# Top_Level.net
KiCad netlist of a schematic drawn in Altium Designer
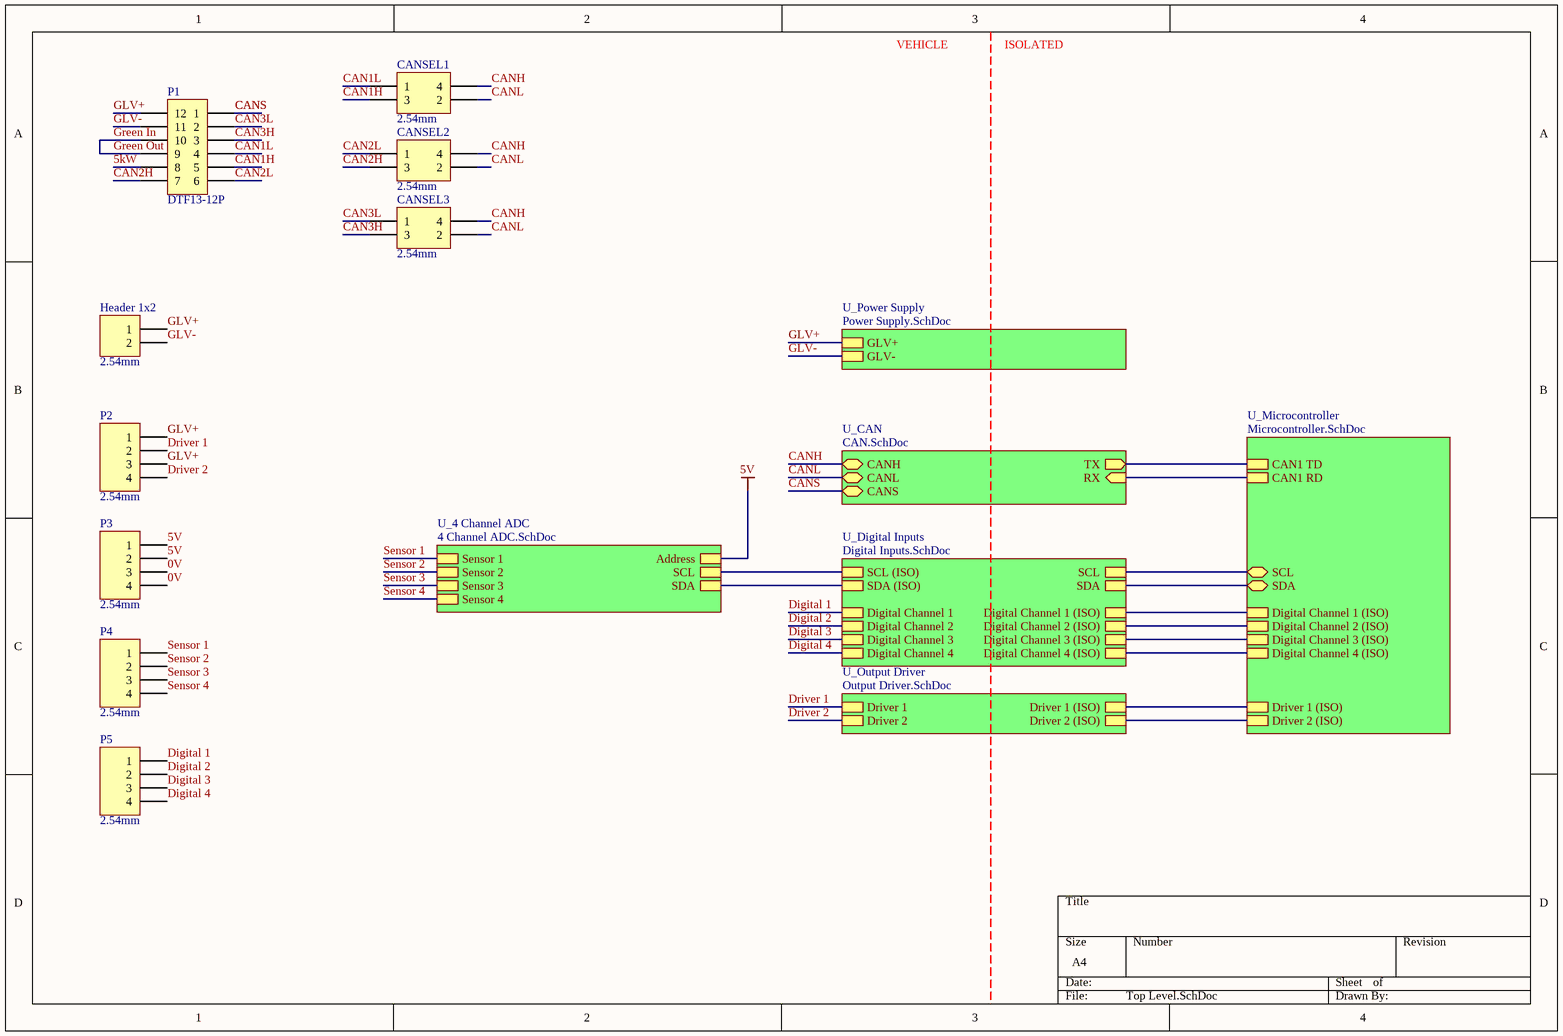
[diagram p0: Top Level.SchDoc]

(export (version "E")
  (design (tool "Eeschema 10.0.6"))
  (components
    (comp (ref "CANSEL1")
      (value "2.54mm")
      (footprint "TH 2.54mm Header 2x2")
      (fields (field (name "PART NUMBER") "TH 2.54mm Header 2x2") (field (name "CONTACT") "NA"))
      (libsource (lib "ts_20-standard-connectors") (part "Header 2x2"))
    )
    (comp (ref "CANSEL2")
      (value "2.54mm")
      (footprint "TH 2.54mm Header 2x2")
      (fields (field (name "PART NUMBER") "TH 2.54mm Header 2x2") (field (name "CONTACT") "NA"))
      (libsource (lib "ts_20-standard-connectors") (part "Header 2x2"))
    )
    (comp (ref "CANSEL3")
      (value "2.54mm")
      (footprint "TH 2.54mm Header 2x2")
      (fields (field (name "PART NUMBER") "TH 2.54mm Header 2x2") (field (name "CONTACT") "NA"))
      (libsource (lib "ts_20-standard-connectors") (part "Header 2x2"))
    )
    (comp (ref "Header 1x2")
      (value "2.54mm")
      (footprint "TH 5.08mm Header 1x2")
      (fields (field (name "PART NUMBER") "TH 5.08mm Header 1x2") (field (name "CONTACT") "NA"))
      (libsource (lib "ts_20-standard-connectors") (part "Header 1x2"))
    )
    (comp (ref "P1")
      (value "DTF13-12P")
      (footprint "DTF13-12P")
      (fields (field (name "DIGIKEY PART NUMBER") "1734-1861-ND") (field (name "CONTACT") "Copper Alloy"))
      (libsource (lib "ts_20-standard-connectors") (part "DT13-12P"))
    )
    (comp (ref "P2")
      (value "2.54mm")
      (footprint "TH 5.08mm Header 1x4")
      (fields (field (name "PART NUMBER") "TH 5.08mm Header 1x4") (field (name "CONTACT") "NA"))
      (libsource (lib "ts_20-standard-connectors") (part "Header 1x4"))
    )
    (comp (ref "P3")
      (value "2.54mm")
      (footprint "TH 5.08mm Header 1x4")
      (fields (field (name "PART NUMBER") "TH 5.08mm Header 1x4") (field (name "CONTACT") "NA"))
      (libsource (lib "ts_20-standard-connectors") (part "Header 1x4"))
    )
    (comp (ref "P4")
      (value "2.54mm")
      (footprint "TH 5.08mm Header 1x4")
      (fields (field (name "PART NUMBER") "TH 5.08mm Header 1x4") (field (name "CONTACT") "NA"))
      (libsource (lib "ts_20-standard-connectors") (part "Header 1x4"))
    )
    (comp (ref "P5")
      (value "2.54mm")
      (footprint "TH 5.08mm Header 1x4")
      (fields (field (name "PART NUMBER") "TH 5.08mm Header 1x4") (field (name "CONTACT") "NA"))
      (libsource (lib "ts_20-standard-connectors") (part "Header 1x4"))
    )
  )
  (nets
    (net (code "1") (name "/0V") (class "Default")
      (node (ref "P3") (pin "3") (pinfunction "3_3") (pintype "passive"))
      (node (ref "P3") (pin "4") (pinfunction "4_4") (pintype "passive"))
    )
    (net (code "2") (name "/5kW") (class "Default")
      (node (ref "P1") (pin "8") (pinfunction "8_8") (pintype "passive"))
    )
    (net (code "4") (name "/CAN1H") (class "Default")
      (node (ref "CANSEL1") (pin "3") (pinfunction "3_3") (pintype "passive"))
      (node (ref "P1") (pin "5") (pinfunction "5_5") (pintype "power_in"))
    )
    (net (code "5") (name "/CAN1L") (class "Default")
      (node (ref "CANSEL1") (pin "1") (pinfunction "1_1") (pintype "passive"))
      (node (ref "P1") (pin "4") (pinfunction "4_4") (pintype "power_in"))
    )
    (net (code "6") (name "/CAN2H") (class "Default")
      (node (ref "CANSEL2") (pin "3") (pinfunction "3_3") (pintype "passive"))
      (node (ref "P1") (pin "7") (pinfunction "7_7") (pintype "passive"))
    )
    (net (code "7") (name "/CAN2L") (class "Default")
      (node (ref "CANSEL2") (pin "1") (pinfunction "1_1") (pintype "passive"))
      (node (ref "P1") (pin "6") (pinfunction "6_6") (pintype "power_in"))
    )
    (net (code "8") (name "/CAN3H") (class "Default")
      (node (ref "CANSEL3") (pin "3") (pinfunction "3_3") (pintype "passive"))
      (node (ref "P1") (pin "3") (pinfunction "3_3") (pintype "power_in"))
    )
    (net (code "9") (name "/CAN3L") (class "Default")
      (node (ref "CANSEL3") (pin "1") (pinfunction "1_1") (pintype "passive"))
      (node (ref "P1") (pin "2") (pinfunction "2_2") (pintype "power_in"))
    )
    (net (code "10") (name "/CANH") (class "Default")
      (node (ref "CANSEL1") (pin "4") (pinfunction "4_4") (pintype "passive"))
      (node (ref "CANSEL2") (pin "4") (pinfunction "4_4") (pintype "passive"))
      (node (ref "CANSEL3") (pin "4") (pinfunction "4_4") (pintype "passive"))
    )
    (net (code "11") (name "/CANL") (class "Default")
      (node (ref "CANSEL1") (pin "2") (pinfunction "2_2") (pintype "passive"))
      (node (ref "CANSEL2") (pin "2") (pinfunction "2_2") (pintype "passive"))
      (node (ref "CANSEL3") (pin "2") (pinfunction "2_2") (pintype "passive"))
    )
    (net (code "12") (name "/CANS") (class "Default")
      (node (ref "P1") (pin "1") (pinfunction "1_1") (pintype "power_in"))
    )
    (net (code "13") (name "/Digital 1") (class "Default")
      (node (ref "P5") (pin "1") (pinfunction "1_1") (pintype "passive"))
    )
    (net (code "14") (name "/Digital 2") (class "Default")
      (node (ref "P5") (pin "2") (pinfunction "2_2") (pintype "passive"))
    )
    (net (code "15") (name "/Digital 3") (class "Default")
      (node (ref "P5") (pin "3") (pinfunction "3_3") (pintype "passive"))
    )
    (net (code "16") (name "/Digital 4") (class "Default")
      (node (ref "P5") (pin "4") (pinfunction "4_4") (pintype "passive"))
    )
    (net (code "21") (name "/Driver 1") (class "Default")
      (node (ref "P2") (pin "2") (pinfunction "2_2") (pintype "passive"))
    )
    (net (code "23") (name "/Driver 2") (class "Default")
      (node (ref "P2") (pin "4") (pinfunction "4_4") (pintype "passive"))
    )
    (net (code "25") (name "/GLV+") (class "Default")
      (node (ref "Header 1x2") (pin "1") (pinfunction "1_1") (pintype "passive"))
      (node (ref "P1") (pin "12") (pinfunction "12_12") (pintype "passive"))
      (node (ref "P2") (pin "1") (pinfunction "1_1") (pintype "passive"))
      (node (ref "P2") (pin "3") (pinfunction "3_3") (pintype "passive"))
    )
    (net (code "26") (name "/GLV-") (class "Default")
      (node (ref "Header 1x2") (pin "2") (pinfunction "2_2") (pintype "passive"))
      (node (ref "P1") (pin "11") (pinfunction "11_11") (pintype "passive"))
    )
    (net (code "27") (name "/Green In") (class "Default")
      (node (ref "P1") (pin "10") (pinfunction "10_10") (pintype "passive"))
      (node (ref "P1") (pin "9") (pinfunction "9_9") (pintype "passive"))
    )
    (net (code "32") (name "/Sensor 1") (class "Default")
      (node (ref "P4") (pin "1") (pinfunction "1_1") (pintype "passive"))
    )
    (net (code "33") (name "/Sensor 2") (class "Default")
      (node (ref "P4") (pin "2") (pinfunction "2_2") (pintype "passive"))
    )
    (net (code "34") (name "/Sensor 3") (class "Default")
      (node (ref "P4") (pin "3") (pinfunction "3_3") (pintype "passive"))
    )
    (net (code "35") (name "/Sensor 4") (class "Default")
      (node (ref "P4") (pin "4") (pinfunction "4_4") (pintype "passive"))
    )
    (net (code "37") (name "5V") (class "Default")
      (node (ref "P3") (pin "1") (pinfunction "1_1") (pintype "passive"))
      (node (ref "P3") (pin "2") (pinfunction "2_2") (pintype "passive"))
    )
  )
)
